# Synth_Shield.net
KiCad netlist of a schematic drawn in Altium Designer
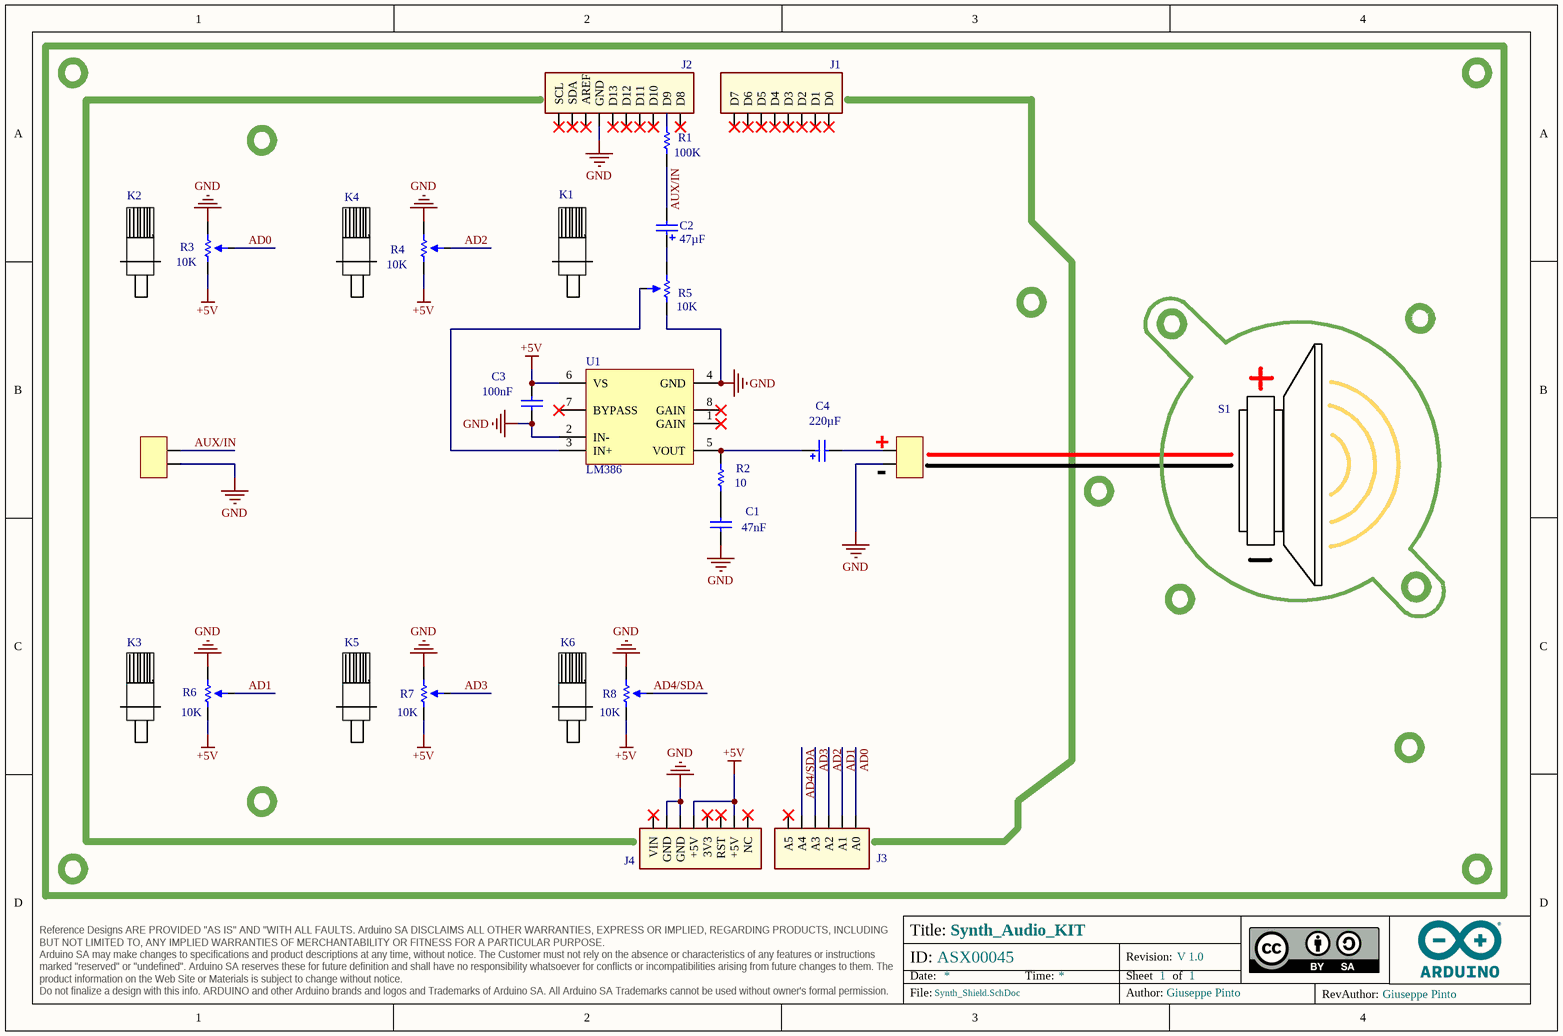
[diagram p0: Synth_Shield.SchDoc]

(export (version "E")
  (design (tool "Eeschema 10.0.6"))
  (components
    (comp (ref "C1")
      (value "47nF")
      (footprint "TS170R1H473KSABB0R")
      (description "CAP THD 47nF 50V C0G 5%")
      (fields (field (name "PART NUMBER") "TS170R1H473KSABB0R") (field (name "MANUFACTURER") "Suntan"))
      (libsource (lib "Clean") (part "CAP"))
    )
    (comp (ref "C2")
      (value "47µF")
      (footprint "EKF476M1EE05TU")
      (description "CAP ALUM POL THD 47uF 25V")
      (fields (field (name "VOLTAGE") "25V") (field (name "PART NUMBER") "EKF476M1EE05TU"))
      (libsource (lib "Clean") (part "CAP-POL"))
    )
    (comp (ref "C3")
      (value "100nF")
      (footprint "B32529C0104J289")
      (description "CAP THD 100NF 63V POLIESTER")
      (fields (field (name "PART NUMBER") "B32529C0104J289") (field (name "MANUFACTURER") "EPCOS"))
      (libsource (lib "Clean") (part "CAP"))
    )
    (comp (ref "C4")
      (value "220µF")
      (footprint "EKM227M1EE11TUSAP")
      (description "CAP ALUM POL THD 220uF 25V")
      (fields (field (name "VOLTAGE") "25V") (field (name "PART NUMBER") "EKM227M1EE11TUSAP"))
      (libsource (lib "Clean") (part "CAP-POL"))
    )
    (comp (ref "J1")
      (value "PH1-08-UA")
      (footprint "CONN STRIP 2.54 PIN HEADER DIP 180° 1x 8 PIN GOLD FLASH")
      (description "CONN STRIP 2.54 PIN HEADER DIP 180° 1x 8 PIN GOLD FLASH")
      (fields (field (name "MANUFACTURER") "4UCONN"))
      (libsource (lib "Clean") (part "PH1-08-UA"))
    )
    (comp (ref "J2")
      (value "PH1-10-UA")
      (footprint "CONN STRIP 2.54 PIN HEADER DIP 180° 1x 10 PIN GOLD FLASH")
      (description "CONN STRIP 2.54 PIN HEADER DIP 180° 1x 10 PIN GOLD FLASH")
      (fields (field (name "MANUFACTURER") "4UCONN"))
      (libsource (lib "Clean") (part "PH1-10-UA"))
    )
    (comp (ref "J3")
      (value "PH1-06-UA")
      (footprint "2.54 PIN HEADER DIP 180° 1x 6 PIN GOLD FLASH")
      (description "CONN STRIP 2.54 PIN HEADER DIP 180° 1x 6 PIN GOLD FLASH")
      (fields (field (name "MANUFACTURER") "4UCONN"))
      (libsource (lib "Clean") (part "PH1-06-UA"))
    )
    (comp (ref "J4")
      (value "PH1-08-UA")
      (footprint "CONN STRIP 2.54 PIN HEADER DIP 180° 1x 8 PIN GOLD FLASH")
      (description "CONN STRIP 2.54 PIN HEADER DIP 180° 1x 8 PIN GOLD FLASH")
      (fields (field (name "MANUFACTURER") "4UCONN"))
      (libsource (lib "") (part "PH1-08-UA_1"))
    )
    (comp (ref "J5")
      (value "MK125002GO")
      (footprint "MK125002GO")
      (description "CONN MORS.CS 2v p3,5 10A aLING.VER")
      (fields (field (name "MANUFACTURER") "Adimpex"))
      (libsource (lib "Clean") (part "MK125002GO"))
    )
    (comp (ref "J6")
      (value "MK125002GO")
      (footprint "MK125002GO")
      (description "CONN MORS.CS 2v p3,5 10A aLING.VER")
      (fields (field (name "MANUFACTURER") "Adimpex"))
      (libsource (lib "") (part "MK125002GO_1"))
    )
    (comp (ref "K1")
      (value "KNOB TRIMMER")
      (footprint "0147")
      (description "KNOB TRIMMER ALBERINO.CA9 L23 D6/9mm")
      (fields (field (name "PART NUMBER") "9006") (field (name "MANUFACTURER") "T2"))
      (libsource (lib "Clean") (part "0147"))
    )
    (comp (ref "K2")
      (value "KNOB TRIMMER")
      (footprint "0147")
      (description "KNOB TRIMMER ALBERINO.CA9 L23 D6/9mm")
      (fields (field (name "PART NUMBER") "9006") (field (name "MANUFACTURER") "T2"))
      (libsource (lib "Clean") (part "0147"))
    )
    (comp (ref "K3")
      (value "KNOB TRIMMER")
      (footprint "0147")
      (description "KNOB TRIMMER ALBERINO.CA9 L23 D6/9mm")
      (fields (field (name "PART NUMBER") "9006") (field (name "MANUFACTURER") "T2"))
      (libsource (lib "Clean") (part "0147"))
    )
    (comp (ref "K4")
      (value "KNOB TRIMMER")
      (footprint "0147")
      (description "KNOB TRIMMER ALBERINO.CA9 L23 D6/9mm")
      (fields (field (name "PART NUMBER") "9006") (field (name "MANUFACTURER") "T2"))
      (libsource (lib "Clean") (part "0147"))
    )
    (comp (ref "K5")
      (value "KNOB TRIMMER")
      (footprint "0147")
      (description "KNOB TRIMMER ALBERINO.CA9 L23 D6/9mm")
      (fields (field (name "PART NUMBER") "9006") (field (name "MANUFACTURER") "T2"))
      (libsource (lib "Clean") (part "0147"))
    )
    (comp (ref "K6")
      (value "KNOB TRIMMER")
      (footprint "0147")
      (description "KNOB TRIMMER ALBERINO.CA9 L23 D6/9mm")
      (fields (field (name "PART NUMBER") "9006") (field (name "MANUFACTURER") "T2"))
      (libsource (lib "Clean") (part "0147"))
    )
    (comp (ref "R1")
      (value "100K")
      (footprint "-0-1623930-1")
      (description "RES FIXED THD 1/4W 5% 100K")
      (fields (field (name "TOLERANCE") "5%") (field (name "POWER") "330mW"))
      (libsource (lib "Clean") (part "RES"))
    )
    (comp (ref "R2")
      (value "10")
      (footprint "R0230")
      (description "RES FIXED THD 1/4W 5% 10R")
      (fields (field (name "TOLERANCE") "5%") (field (name "POWER") "330mW"))
      (libsource (lib "Clean") (part "RES"))
    )
    (comp (ref "R3")
      (value "CA9MV10-10KA2020")
      (footprint "New footprint 1")
      (description "Potentiometer 10kilohm - TRIMMER")
      (fields (field (name "VALUE MAX") "10K"))
      (libsource (lib "Clean") (part "POTENTIOMETER"))
    )
    (comp (ref "R4")
      (value "CA9MV10-10KA2020")
      (footprint "New footprint 1")
      (description "Potentiometer 10kilohm - TRIMMER")
      (fields (field (name "VALUE MAX") "10K"))
      (libsource (lib "Clean") (part "POTENTIOMETER"))
    )
    (comp (ref "R5")
      (value "CA9MV10-10KA2020")
      (footprint "New footprint 1")
      (description "Potentiometer 10kilohm - TRIMMER")
      (fields (field (name "VALUE MAX") "10K"))
      (libsource (lib "Clean") (part "POTENTIOMETER"))
    )
    (comp (ref "R6")
      (value "CA9MV10-10KA2020")
      (footprint "New footprint 1")
      (description "Potentiometer 10kilohm - TRIMMER")
      (fields (field (name "VALUE MAX") "10K"))
      (libsource (lib "Clean") (part "POTENTIOMETER"))
    )
    (comp (ref "R7")
      (value "CA9MV10-10KA2020")
      (footprint "New footprint 1")
      (description "Potentiometer 10kilohm - TRIMMER")
      (fields (field (name "VALUE MAX") "10K"))
      (libsource (lib "Clean") (part "POTENTIOMETER"))
    )
    (comp (ref "R8")
      (value "CA9MV10-10KA2020")
      (footprint "New footprint 1")
      (description "Potentiometer 10kilohm - TRIMMER")
      (fields (field (name "VALUE MAX") "10K"))
      (libsource (lib "Clean") (part "POTENTIOMETER"))
    )
    (comp (ref "S1")
      (value "L50EJ050008WLFLM-002")
      (footprint "L50EJ050008WLFLM-002")
      (description "Paper Speaker 8Ω 1W + Grid  PCB")
      (fields (field (name "MANUFACTURER") "DB Pructs Limited"))
      (libsource (lib "Clean") (part "Paper Speaker 8Ω 1W+ Grid"))
    )
    (comp (ref "U1")
      (value "LM386")
      (footprint "P0008A")
      (description "Audio Amplifier, 0.325W, 1 Channel(s), 1 Func, Bipolar, PDIP8")
      (fields (field (name "PART NUMBER") "LM386N-1/NOPB"))
      (libsource (lib "Clean") (part "AMP-APA-LM386-8"))
    )
  )
  (nets
    (net (code "1") (name "+5V") (class "Default")
      (node (ref "C3") (pin "1") (pinfunction "1_1") (pintype "passive"))
      (node (ref "J4") (pin "2") (pinfunction "+5V_2") (pintype "passive"))
      (node (ref "J4") (pin "5") (pinfunction "+5V_5") (pintype "passive"))
      (node (ref "R3") (pin "3") (pinfunction "3_3") (pintype "passive"))
      (node (ref "R4") (pin "3") (pinfunction "3_3") (pintype "passive"))
      (node (ref "R6") (pin "3") (pinfunction "3_3") (pintype "passive"))
      (node (ref "R7") (pin "3") (pinfunction "3_3") (pintype "passive"))
      (node (ref "R8") (pin "3") (pinfunction "3_3") (pintype "passive"))
      (node (ref "U1") (pin "6") (pinfunction "VS_6") (pintype "power_in"))
    )
    (net (code "2") (name "/AD0") (class "Default")
      (node (ref "J3") (pin "1") (pinfunction "A0_1") (pintype "passive"))
      (node (ref "R3") (pin "2") (pinfunction "2_2") (pintype "passive"))
    )
    (net (code "3") (name "/AD1") (class "Default")
      (node (ref "J3") (pin "2") (pinfunction "A1_2") (pintype "passive"))
      (node (ref "R6") (pin "2") (pinfunction "2_2") (pintype "passive"))
    )
    (net (code "4") (name "/AD2") (class "Default")
      (node (ref "J3") (pin "3") (pinfunction "A2_3") (pintype "passive"))
      (node (ref "R4") (pin "2") (pinfunction "2_2") (pintype "passive"))
    )
    (net (code "5") (name "/AD3") (class "Default")
      (node (ref "J3") (pin "4") (pinfunction "A3_4") (pintype "passive"))
      (node (ref "R7") (pin "2") (pinfunction "2_2") (pintype "passive"))
    )
    (net (code "6") (name "/AD4{slash}SDA") (class "Default")
      (node (ref "J3") (pin "5") (pinfunction "A4_5") (pintype "passive"))
      (node (ref "R8") (pin "2") (pinfunction "2_2") (pintype "passive"))
    )
    (net (code "7") (name "/AUX{slash}IN") (class "Default")
      (node (ref "C2") (pin "1") (pinfunction "1_1") (pintype "passive"))
      (node (ref "J6") (pin "2") (pinfunction "2_2") (pintype "passive"))
      (node (ref "R1") (pin "2") (pinfunction "2_2") (pintype "passive"))
    )
    (net (code "8") (name "GND") (class "Default")
      (node (ref "C1") (pin "2") (pinfunction "2_2") (pintype "passive"))
      (node (ref "C3") (pin "2") (pinfunction "2_2") (pintype "passive"))
      (node (ref "J2") (pin "7") (pinfunction "GND_7") (pintype "passive"))
      (node (ref "J4") (pin "6") (pinfunction "GND_6") (pintype "passive"))
      (node (ref "J4") (pin "7") (pinfunction "GND_7") (pintype "passive"))
      (node (ref "J5") (pin "1") (pinfunction "1_1") (pintype "passive"))
      (node (ref "J6") (pin "1") (pinfunction "1_1") (pintype "passive"))
      (node (ref "R3") (pin "1") (pinfunction "1_1") (pintype "passive"))
      (node (ref "R4") (pin "1") (pinfunction "1_1") (pintype "passive"))
      (node (ref "R5") (pin "1") (pinfunction "1_1") (pintype "passive"))
      (node (ref "R6") (pin "1") (pinfunction "1_1") (pintype "passive"))
      (node (ref "R7") (pin "1") (pinfunction "1_1") (pintype "passive"))
      (node (ref "R8") (pin "1") (pinfunction "1_1") (pintype "passive"))
      (node (ref "U1") (pin "2") (pinfunction "IN-_2") (pintype "passive"))
      (node (ref "U1") (pin "4") (pinfunction "GND_4") (pintype "power_in"))
    )
    (net (code "9") (name "Net-(C1-Pad1)") (class "Default")
      (node (ref "C1") (pin "1") (pinfunction "1_1") (pintype "passive"))
      (node (ref "R2") (pin "2") (pinfunction "2_2") (pintype "passive"))
    )
    (net (code "10") (name "Net-(C2-Pad2)") (class "Default")
      (node (ref "C2") (pin "2") (pinfunction "2_2") (pintype "passive"))
      (node (ref "R5") (pin "3") (pinfunction "3_3") (pintype "passive"))
    )
    (net (code "11") (name "Net-(C4-Pad1)") (class "Default")
      (node (ref "C4") (pin "1") (pinfunction "1_1") (pintype "passive"))
      (node (ref "J5") (pin "2") (pinfunction "2_2") (pintype "passive"))
    )
    (net (code "12") (name "Net-(J2-D9)") (class "Default")
      (node (ref "J2") (pin "2") (pinfunction "D9_2") (pintype "passive"))
      (node (ref "R1") (pin "1") (pinfunction "1_1") (pintype "passive"))
    )
    (net (code "13") (name "Net-(U1-IN+)") (class "Default")
      (node (ref "R5") (pin "2") (pinfunction "2_2") (pintype "passive"))
      (node (ref "U1") (pin "3") (pinfunction "IN+_3") (pintype "passive"))
    )
    (net (code "14") (name "Net-(U1-VOUT)") (class "Default")
      (node (ref "C4") (pin "2") (pinfunction "2_2") (pintype "passive"))
      (node (ref "R2") (pin "1") (pinfunction "1_1") (pintype "passive"))
      (node (ref "U1") (pin "5") (pinfunction "VOUT_5") (pintype "passive"))
    )
    (net (code "15") (name "unconnected-(J1-D0-Pad1)") (class "Default")
      (node (ref "J1") (pin "1") (pinfunction "D0_1") (pintype "passive+no_connect"))
    )
    (net (code "16") (name "unconnected-(J1-D1-Pad2)") (class "Default")
      (node (ref "J1") (pin "2") (pinfunction "D1_2") (pintype "passive+no_connect"))
    )
    (net (code "17") (name "unconnected-(J1-D2-Pad3)") (class "Default")
      (node (ref "J1") (pin "3") (pinfunction "D2_3") (pintype "passive+no_connect"))
    )
    (net (code "18") (name "unconnected-(J1-D3-Pad4)") (class "Default")
      (node (ref "J1") (pin "4") (pinfunction "D3_4") (pintype "passive+no_connect"))
    )
    (net (code "19") (name "unconnected-(J1-D4-Pad5)") (class "Default")
      (node (ref "J1") (pin "5") (pinfunction "D4_5") (pintype "passive+no_connect"))
    )
    (net (code "20") (name "unconnected-(J1-D5-Pad6)") (class "Default")
      (node (ref "J1") (pin "6") (pinfunction "D5_6") (pintype "passive+no_connect"))
    )
    (net (code "21") (name "unconnected-(J1-D6-Pad7)") (class "Default")
      (node (ref "J1") (pin "7") (pinfunction "D6_7") (pintype "passive+no_connect"))
    )
    (net (code "22") (name "unconnected-(J1-D7-Pad8)") (class "Default")
      (node (ref "J1") (pin "8") (pinfunction "D7_8") (pintype "passive+no_connect"))
    )
    (net (code "23") (name "unconnected-(J2-AREF-Pad8)") (class "Default")
      (node (ref "J2") (pin "8") (pinfunction "AREF_8") (pintype "passive+no_connect"))
    )
    (net (code "24") (name "unconnected-(J2-D8-Pad1)") (class "Default")
      (node (ref "J2") (pin "1") (pinfunction "D8_1") (pintype "passive+no_connect"))
    )
    (net (code "25") (name "unconnected-(J2-D10-Pad3)") (class "Default")
      (node (ref "J2") (pin "3") (pinfunction "D10_3") (pintype "passive+no_connect"))
    )
    (net (code "26") (name "unconnected-(J2-D11-Pad4)") (class "Default")
      (node (ref "J2") (pin "4") (pinfunction "D11_4") (pintype "passive+no_connect"))
    )
    (net (code "27") (name "unconnected-(J2-D12-Pad5)") (class "Default")
      (node (ref "J2") (pin "5") (pinfunction "D12_5") (pintype "passive+no_connect"))
    )
    (net (code "28") (name "unconnected-(J2-D13-Pad6)") (class "Default")
      (node (ref "J2") (pin "6") (pinfunction "D13_6") (pintype "passive+no_connect"))
    )
    (net (code "29") (name "unconnected-(J2-SCL-Pad10)") (class "Default")
      (node (ref "J2") (pin "10") (pinfunction "SCL_10") (pintype "passive+no_connect"))
    )
    (net (code "30") (name "unconnected-(J2-SDA-Pad9)") (class "Default")
      (node (ref "J2") (pin "9") (pinfunction "SDA_9") (pintype "passive+no_connect"))
    )
    (net (code "31") (name "unconnected-(J3-A5-Pad6)") (class "Default")
      (node (ref "J3") (pin "6") (pinfunction "A5_6") (pintype "passive+no_connect"))
    )
    (net (code "32") (name "unconnected-(J4-3V3-Pad4)") (class "Default")
      (node (ref "J4") (pin "4") (pinfunction "3V3_4") (pintype "passive+no_connect"))
    )
    (net (code "33") (name "unconnected-(J4-NC-Pad1)") (class "Default")
      (node (ref "J4") (pin "1") (pinfunction "NC_1") (pintype "passive+no_connect"))
    )
    (net (code "34") (name "unconnected-(J4-RST-Pad3)") (class "Default")
      (node (ref "J4") (pin "3") (pinfunction "RST_3") (pintype "passive+no_connect"))
    )
    (net (code "35") (name "unconnected-(J4-VIN-Pad8)") (class "Default")
      (node (ref "J4") (pin "8") (pinfunction "VIN_8") (pintype "passive+no_connect"))
    )
    (net (code "36") (name "unconnected-(U1-BYPASS-Pad7)") (class "Default")
      (node (ref "U1") (pin "7") (pinfunction "BYPASS_7") (pintype "passive+no_connect"))
    )
    (net (code "37") (name "unconnected-(U1-GAIN-Pad1)") (class "Default")
      (node (ref "U1") (pin "1") (pinfunction "GAIN_1") (pintype "passive+no_connect"))
    )
    (net (code "38") (name "unconnected-(U1-GAIN-Pad8)") (class "Default")
      (node (ref "U1") (pin "8") (pinfunction "GAIN_8") (pintype "passive+no_connect"))
    )
  )
)
